# No_Internet_Game_Robot_2021-07-26.net
KiCad netlist of a schematic drawn in EasyEDA
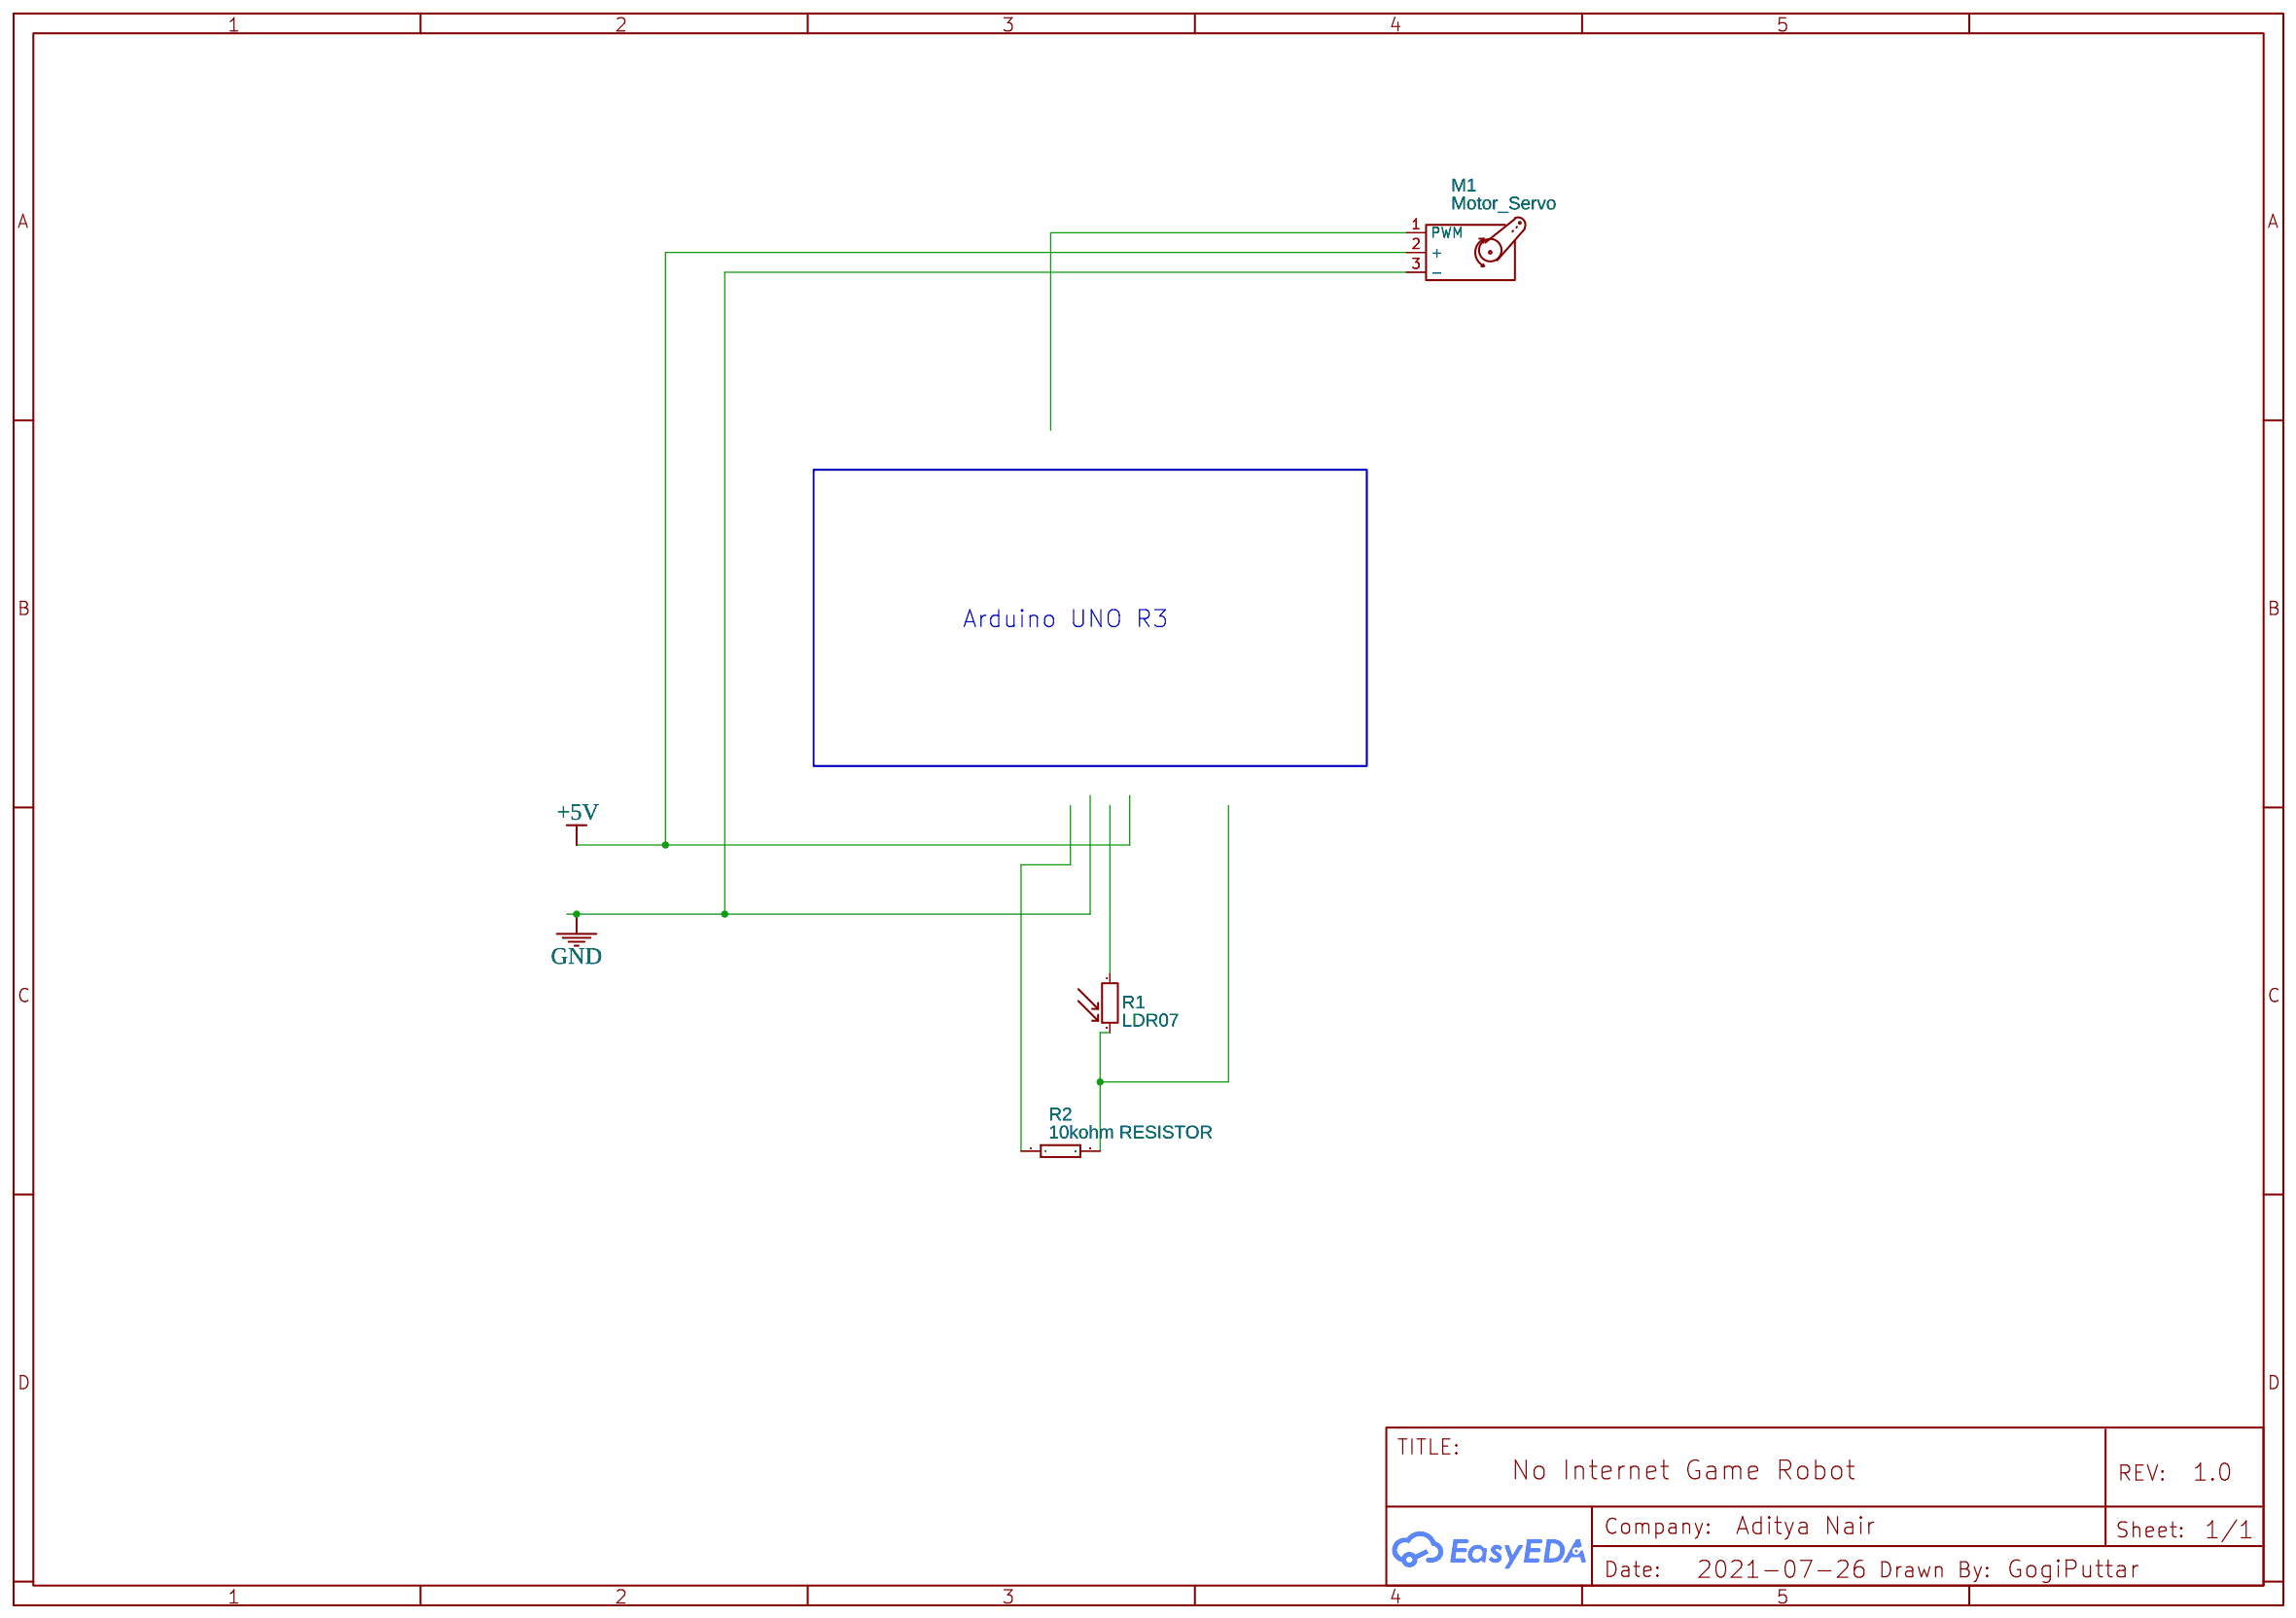
[diagram p0: schematic sheet]

(export (version "E")
  (design (tool "Eeschema 10.0.6"))
  (components
    (comp (ref "M1") (value "Motor_Servo") (libsource (lib "") (part "Motor_Servo")))
    (comp (ref "R1") (value "LDR07") (libsource (lib "") (part "LDR07")))
    (comp (ref "R2") (value "10kohm RESISTOR") (libsource (lib "") (part "RESISTOR")))
  )
  (nets
    (net (code "1") (name "+5V") (class "Default")
      (node (ref "M1") (pin "2") (pinfunction "+_2") (pintype "unspecified"))
    )
    (net (code "2") (name "GND") (class "Default")
      (node (ref "M1") (pin "3") (pinfunction "-_3") (pintype "unspecified"))
    )
    (net (code "3") (name "Net-(R1-Pad2)") (class "Default")
      (node (ref "R1") (pin "2") (pintype "unspecified"))
      (node (ref "R2") (pin "2") (pinfunction "2_2") (pintype "unspecified"))
    )
    (net (code "4") (name "unconnected-(M1-PWM-Pad1)") (class "Default")
      (node (ref "M1") (pin "1") (pinfunction "PWM_1") (pintype "unspecified"))
    )
    (net (code "5") (name "unconnected-(R1-Pad1)") (class "Default")
      (node (ref "R1") (pin "1") (pintype "unspecified"))
    )
    (net (code "6") (name "unconnected-(R2-Pad1)") (class "Default")
      (node (ref "R2") (pin "1") (pinfunction "1_1") (pintype "unspecified"))
    )
  )
)
